# W506X.net
KiCad netlist of a schematic drawn in EAGLE
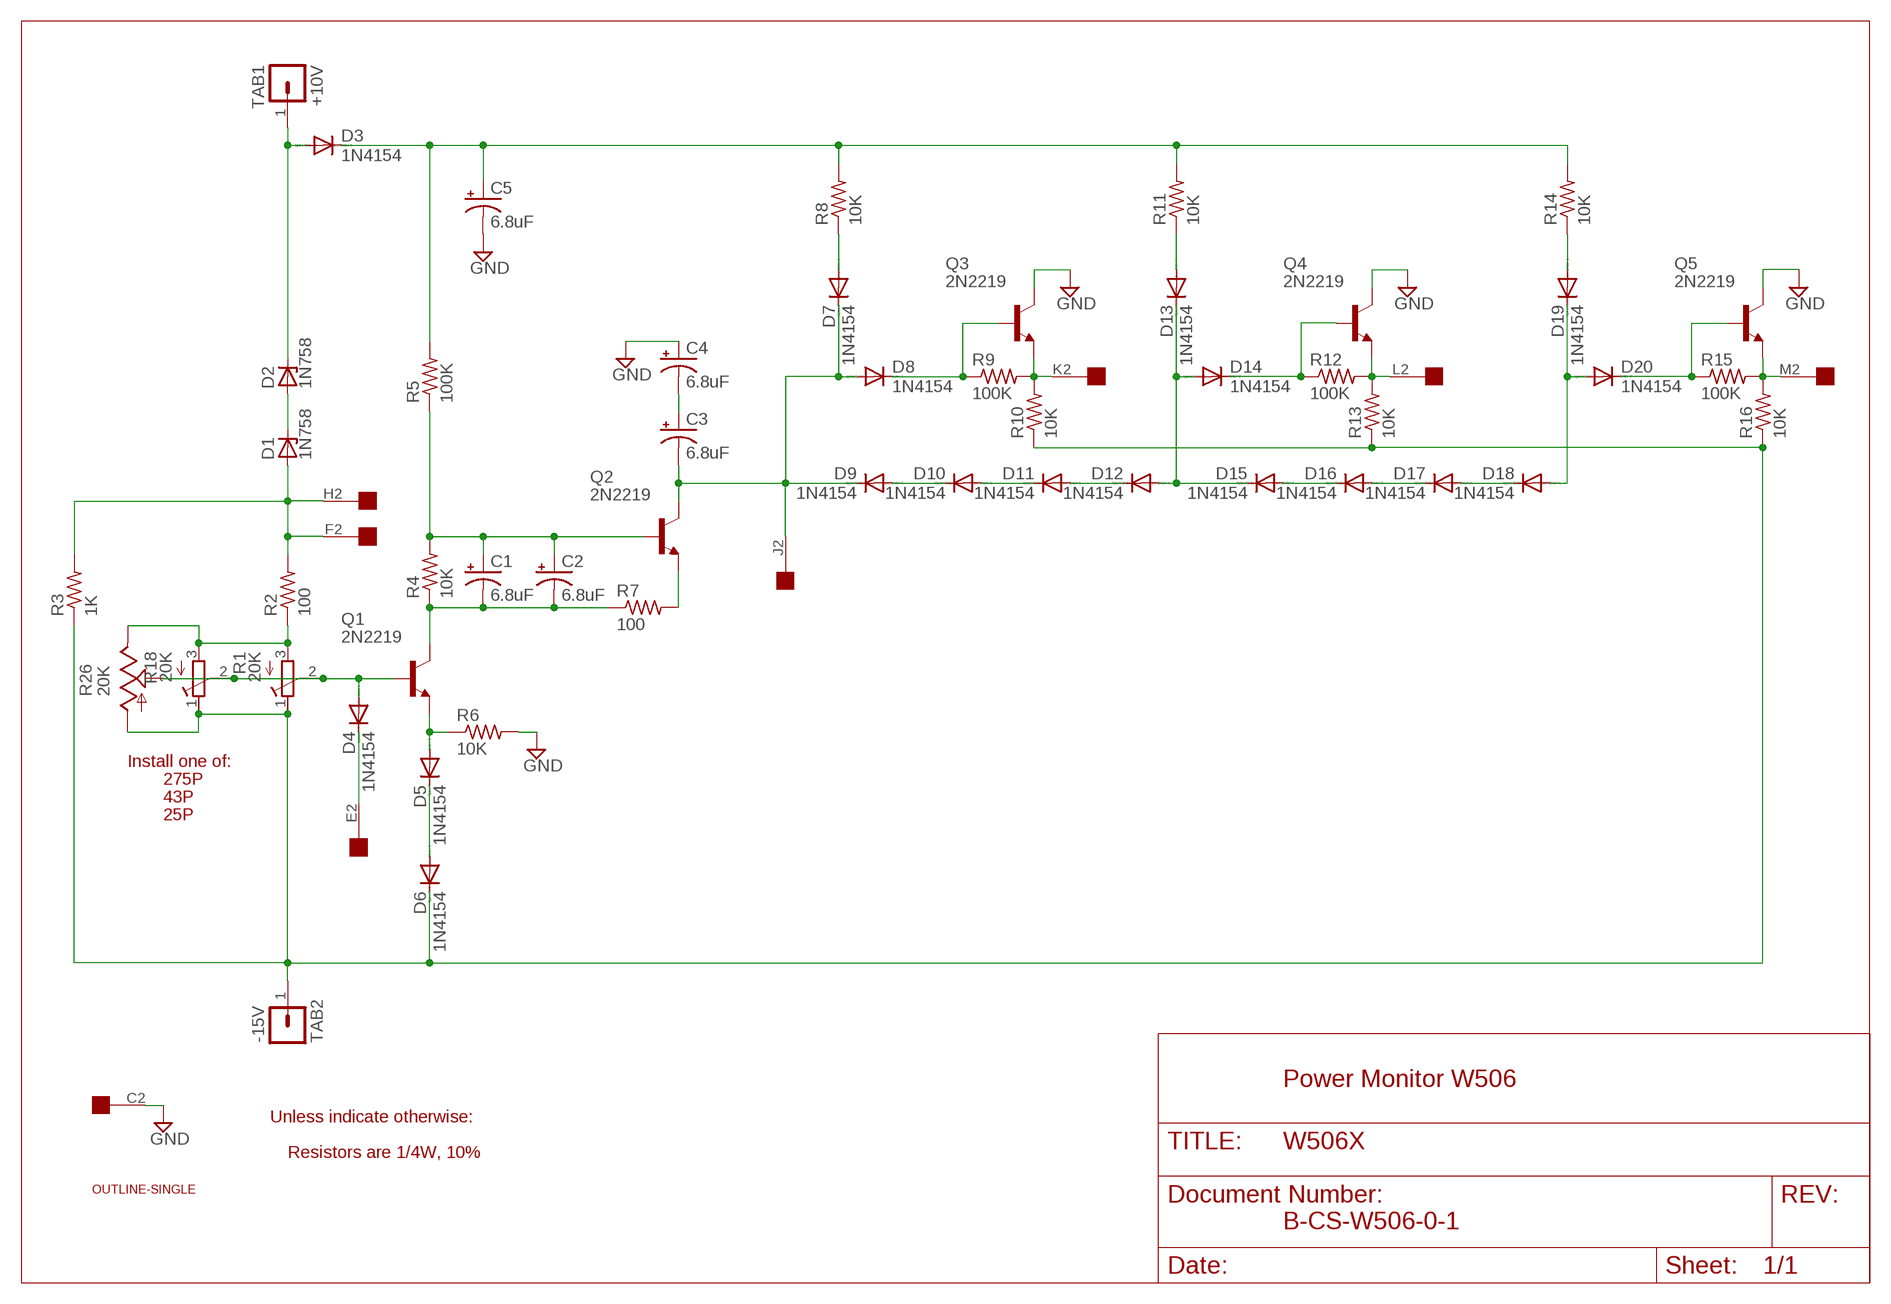
[diagram p0: schematic, sheet 1]

(export (version "E")
  (design (tool "Eeschema 10.0.6"))
  (components
    (comp (ref "C1")
      (value "6.8uF")
      (footprint "eagle-import:E15-5")
      (libsource (lib "eagle-import") (part "CPOL-USE15-5AXIAL"))
    )
    (comp (ref "C2")
      (value "6.8uF")
      (footprint "eagle-import:E15-5")
      (libsource (lib "eagle-import") (part "CPOL-USE15-5AXIAL"))
    )
    (comp (ref "C3")
      (value "6.8uF")
      (footprint "eagle-import:E15-5")
      (libsource (lib "eagle-import") (part "CPOL-USE15-5AXIAL"))
    )
    (comp (ref "C4")
      (value "6.8uF")
      (footprint "eagle-import:E15-5")
      (libsource (lib "eagle-import") (part "CPOL-USE15-5AXIAL"))
    )
    (comp (ref "C5")
      (value "6.8uF")
      (footprint "eagle-import:E15-5")
      (libsource (lib "eagle-import") (part "CPOL-USE15-5AXIAL"))
    )
    (comp (ref "D1")
      (value "1N758")
      (footprint "eagle-import:DO35Z10")
      (libsource (lib "eagle-import") (part "ZENER-DIODEDO35Z10"))
    )
    (comp (ref "D2")
      (value "1N758")
      (footprint "eagle-import:DO35Z10")
      (libsource (lib "eagle-import") (part "ZENER-DIODEDO35Z10"))
    )
    (comp (ref "D3")
      (value "1N4154")
      (footprint "eagle-import:DO35-10")
      (libsource (lib "eagle-import") (part "1N4148DO35-10"))
    )
    (comp (ref "D4")
      (value "1N4154")
      (footprint "eagle-import:DO35-10")
      (libsource (lib "eagle-import") (part "1N4148DO35-10"))
    )
    (comp (ref "D5")
      (value "1N4154")
      (footprint "eagle-import:DO35-10")
      (libsource (lib "eagle-import") (part "1N4148DO35-10"))
    )
    (comp (ref "D6")
      (value "1N4154")
      (footprint "eagle-import:DO35-10")
      (libsource (lib "eagle-import") (part "1N4148DO35-10"))
    )
    (comp (ref "D7")
      (value "1N4154")
      (footprint "eagle-import:DO35-10")
      (libsource (lib "eagle-import") (part "1N4148DO35-10"))
    )
    (comp (ref "D8")
      (value "1N4154")
      (footprint "eagle-import:DO35-10")
      (libsource (lib "eagle-import") (part "1N4148DO35-10"))
    )
    (comp (ref "D9")
      (value "1N4154")
      (footprint "eagle-import:DO35-10")
      (libsource (lib "eagle-import") (part "1N4148DO35-10"))
    )
    (comp (ref "D10")
      (value "1N4154")
      (footprint "eagle-import:DO35-10")
      (libsource (lib "eagle-import") (part "1N4148DO35-10"))
    )
    (comp (ref "D11")
      (value "1N4154")
      (footprint "eagle-import:DO35-10")
      (libsource (lib "eagle-import") (part "1N4148DO35-10"))
    )
    (comp (ref "D12")
      (value "1N4154")
      (footprint "eagle-import:DO35-10")
      (libsource (lib "eagle-import") (part "1N4148DO35-10"))
    )
    (comp (ref "D13")
      (value "1N4154")
      (footprint "eagle-import:DO35-10")
      (libsource (lib "eagle-import") (part "1N4148DO35-10"))
    )
    (comp (ref "D14")
      (value "1N4154")
      (footprint "eagle-import:DO35-10")
      (libsource (lib "eagle-import") (part "1N4148DO35-10"))
    )
    (comp (ref "D15")
      (value "1N4154")
      (footprint "eagle-import:DO35-10")
      (libsource (lib "eagle-import") (part "1N4148DO35-10"))
    )
    (comp (ref "D16")
      (value "1N4154")
      (footprint "eagle-import:DO35-10")
      (libsource (lib "eagle-import") (part "1N4148DO35-10"))
    )
    (comp (ref "D17")
      (value "1N4154")
      (footprint "eagle-import:DO35-10")
      (libsource (lib "eagle-import") (part "1N4148DO35-10"))
    )
    (comp (ref "D18")
      (value "1N4154")
      (footprint "eagle-import:DO35-10")
      (libsource (lib "eagle-import") (part "1N4148DO35-10"))
    )
    (comp (ref "D19")
      (value "1N4154")
      (footprint "eagle-import:DO35-10")
      (libsource (lib "eagle-import") (part "1N4148DO35-10"))
    )
    (comp (ref "D20")
      (value "1N4154")
      (footprint "eagle-import:DO35-10")
      (libsource (lib "eagle-import") (part "1N4148DO35-10"))
    )
    (comp (ref "EDGE")
      (value "EDGE-1")
      (footprint "eagle-import:EDGE-CON1")
      (libsource (lib "eagle-import") (part "EDGE-1"))
    )
    (comp (ref "Q1")
      (value "2N2219")
      (footprint "eagle-import:TO5")
      (libsource (lib "eagle-import") (part "2N2102"))
    )
    (comp (ref "Q2")
      (value "2N2219")
      (footprint "eagle-import:TO5")
      (libsource (lib "eagle-import") (part "2N2102"))
    )
    (comp (ref "Q3")
      (value "2N2219")
      (footprint "eagle-import:TO5")
      (libsource (lib "eagle-import") (part "2N2102"))
    )
    (comp (ref "Q4")
      (value "2N2219")
      (footprint "eagle-import:TO5")
      (libsource (lib "eagle-import") (part "2N2102"))
    )
    (comp (ref "Q5")
      (value "2N2219")
      (footprint "eagle-import:TO5")
      (libsource (lib "eagle-import") (part "2N2102"))
    )
    (comp (ref "R1")
      (value "20K")
      (footprint "eagle-import:3006Y")
      (libsource (lib "eagle-import") (part "275P"))
    )
    (comp (ref "R2")
      (value "100")
      (footprint "eagle-import:0207_10")
      (libsource (lib "eagle-import") (part "R-US_0207/10"))
    )
    (comp (ref "R3")
      (value "1K")
      (footprint "eagle-import:0207_10")
      (libsource (lib "eagle-import") (part "R-US_0207/10"))
    )
    (comp (ref "R4")
      (value "10K")
      (footprint "eagle-import:0207_10")
      (libsource (lib "eagle-import") (part "R-US_0207/10"))
    )
    (comp (ref "R5")
      (value "100K")
      (footprint "eagle-import:0207_10")
      (libsource (lib "eagle-import") (part "R-US_0207/10"))
    )
    (comp (ref "R6")
      (value "10K")
      (footprint "eagle-import:0207_10")
      (libsource (lib "eagle-import") (part "R-US_0207/10"))
    )
    (comp (ref "R7")
      (value "100")
      (footprint "eagle-import:0207_10")
      (libsource (lib "eagle-import") (part "R-US_0207/10"))
    )
    (comp (ref "R8")
      (value "10K")
      (footprint "eagle-import:0207_10")
      (libsource (lib "eagle-import") (part "R-US_0207/10"))
    )
    (comp (ref "R9")
      (value "100K")
      (footprint "eagle-import:0207_10")
      (libsource (lib "eagle-import") (part "R-US_0207/10"))
    )
    (comp (ref "R10")
      (value "10K")
      (footprint "eagle-import:0207_10")
      (libsource (lib "eagle-import") (part "R-US_0207/10"))
    )
    (comp (ref "R11")
      (value "10K")
      (footprint "eagle-import:0207_10")
      (libsource (lib "eagle-import") (part "R-US_0207/10"))
    )
    (comp (ref "R12")
      (value "100K")
      (footprint "eagle-import:0207_10")
      (libsource (lib "eagle-import") (part "R-US_0207/10"))
    )
    (comp (ref "R13")
      (value "10K")
      (footprint "eagle-import:0207_10")
      (libsource (lib "eagle-import") (part "R-US_0207/10"))
    )
    (comp (ref "R14")
      (value "10K")
      (footprint "eagle-import:0207_10")
      (libsource (lib "eagle-import") (part "R-US_0207/10"))
    )
    (comp (ref "R15")
      (value "100K")
      (footprint "eagle-import:0207_10")
      (libsource (lib "eagle-import") (part "R-US_0207/10"))
    )
    (comp (ref "R16")
      (value "10K")
      (footprint "eagle-import:0207_10")
      (libsource (lib "eagle-import") (part "R-US_0207/10"))
    )
    (comp (ref "R18")
      (value "20K")
      (footprint "eagle-import:RTRIM43P")
      (libsource (lib "eagle-import") (part "R-TRIMM43P"))
    )
    (comp (ref "R26")
      (value "20K")
      (footprint "eagle-import:B25P")
      (libsource (lib "eagle-import") (part "TRIM_US-B25P"))
    )
    (comp (ref "TAB1")
      (value "+10V")
      (footprint "eagle-import:SPADELUG")
      (libsource (lib "eagle-import") (part "LUG"))
    )
    (comp (ref "TAB2")
      (value "-15V")
      (footprint "eagle-import:SPADELUG")
      (libsource (lib "eagle-import") (part "LUG"))
    )
    (comp (ref "U$1")
      (value "OUTLINE-SINGLE")
      (footprint "eagle-import:SINGLE")
      (libsource (lib "eagle-import") (part "OUTLINE-SINGLE"))
    )
  )
  (nets
    (net (code "1") (name "GND") (class "Default")
      (node (ref "C4") (pin "+") (pinfunction "+_+") (pintype "passive"))
      (node (ref "C5") (pin "-") (pinfunction "-_-") (pintype "passive"))
      (node (ref "EDGE") (pin "C2") (pinfunction "1_C2") (pintype "bidirectional"))
      (node (ref "Q3") (pin "3") (pinfunction "C_3") (pintype "passive"))
      (node (ref "Q4") (pin "3") (pinfunction "C_3") (pintype "passive"))
      (node (ref "Q5") (pin "3") (pinfunction "C_3") (pintype "passive"))
      (node (ref "R6") (pin "2") (pinfunction "2_2") (pintype "passive"))
    )
    (net (code "2") (name "Net-(C3-Pad+)") (class "Default")
      (node (ref "C3") (pin "+") (pinfunction "+_+") (pintype "passive"))
      (node (ref "C4") (pin "-") (pinfunction "-_-") (pintype "passive"))
    )
    (net (code "3") (name "Net-(C5-Pad+)") (class "Default")
      (node (ref "C5") (pin "+") (pinfunction "+_+") (pintype "passive"))
      (node (ref "D3") (pin "C") (pinfunction "C_C") (pintype "passive"))
      (node (ref "R11") (pin "2") (pinfunction "2_2") (pintype "passive"))
      (node (ref "R14") (pin "2") (pinfunction "2_2") (pintype "passive"))
      (node (ref "R5") (pin "2") (pinfunction "2_2") (pintype "passive"))
      (node (ref "R8") (pin "2") (pinfunction "2_2") (pintype "passive"))
    )
    (net (code "4") (name "Net-(D1-PadC)") (class "Default")
      (node (ref "D1") (pin "C") (pinfunction "C_C") (pintype "passive"))
      (node (ref "D2") (pin "A") (pinfunction "A_A") (pintype "passive"))
    )
    (net (code "5") (name "Net-(D2-PadC)") (class "Default")
      (node (ref "D2") (pin "C") (pinfunction "C_C") (pintype "passive"))
      (node (ref "D3") (pin "A") (pinfunction "A_A") (pintype "passive"))
      (node (ref "TAB1") (pin "1") (pinfunction "1_1") (pintype "passive"))
    )
    (net (code "6") (name "Net-(D5-PadC)") (class "Default")
      (node (ref "D5") (pin "C") (pinfunction "C_C") (pintype "passive"))
      (node (ref "D6") (pin "A") (pinfunction "A_A") (pintype "passive"))
    )
    (net (code "7") (name "Net-(D7-PadA)") (class "Default")
      (node (ref "D7") (pin "A") (pinfunction "A_A") (pintype "passive"))
      (node (ref "R8") (pin "1") (pinfunction "1_1") (pintype "passive"))
    )
    (net (code "8") (name "Net-(D10-PadA)") (class "Default")
      (node (ref "D10") (pin "A") (pinfunction "A_A") (pintype "passive"))
      (node (ref "D11") (pin "C") (pinfunction "C_C") (pintype "passive"))
    )
    (net (code "9") (name "Net-(D10-PadC)") (class "Default")
      (node (ref "D10") (pin "C") (pinfunction "C_C") (pintype "passive"))
      (node (ref "D9") (pin "A") (pinfunction "A_A") (pintype "passive"))
    )
    (net (code "10") (name "Net-(D11-PadA)") (class "Default")
      (node (ref "D11") (pin "A") (pinfunction "A_A") (pintype "passive"))
      (node (ref "D12") (pin "C") (pinfunction "C_C") (pintype "passive"))
    )
    (net (code "11") (name "Net-(D12-PadA)") (class "Default")
      (node (ref "D12") (pin "A") (pinfunction "A_A") (pintype "passive"))
      (node (ref "D13") (pin "C") (pinfunction "C_C") (pintype "passive"))
      (node (ref "D14") (pin "A") (pinfunction "A_A") (pintype "passive"))
      (node (ref "D15") (pin "C") (pinfunction "C_C") (pintype "passive"))
    )
    (net (code "12") (name "Net-(D13-PadA)") (class "Default")
      (node (ref "D13") (pin "A") (pinfunction "A_A") (pintype "passive"))
      (node (ref "R11") (pin "1") (pinfunction "1_1") (pintype "passive"))
    )
    (net (code "13") (name "Net-(D15-PadA)") (class "Default")
      (node (ref "D15") (pin "A") (pinfunction "A_A") (pintype "passive"))
      (node (ref "D16") (pin "C") (pinfunction "C_C") (pintype "passive"))
    )
    (net (code "14") (name "Net-(D16-PadA)") (class "Default")
      (node (ref "D16") (pin "A") (pinfunction "A_A") (pintype "passive"))
      (node (ref "D17") (pin "C") (pinfunction "C_C") (pintype "passive"))
    )
    (net (code "15") (name "Net-(D17-PadA)") (class "Default")
      (node (ref "D17") (pin "A") (pinfunction "A_A") (pintype "passive"))
      (node (ref "D18") (pin "C") (pinfunction "C_C") (pintype "passive"))
    )
    (net (code "16") (name "Net-(D18-PadA)") (class "Default")
      (node (ref "D18") (pin "A") (pinfunction "A_A") (pintype "passive"))
      (node (ref "D19") (pin "C") (pinfunction "C_C") (pintype "passive"))
      (node (ref "D20") (pin "A") (pinfunction "A_A") (pintype "passive"))
    )
    (net (code "17") (name "Net-(D19-PadA)") (class "Default")
      (node (ref "D19") (pin "A") (pinfunction "A_A") (pintype "passive"))
      (node (ref "R14") (pin "1") (pinfunction "1_1") (pintype "passive"))
    )
    (net (code "18") (name "Net-(EDGEE-1)") (class "Default")
      (node (ref "D4") (pin "C") (pinfunction "C_C") (pintype "passive"))
      (node (ref "EDGE") (pin "E2") (pinfunction "1_E2") (pintype "bidirectional"))
    )
    (net (code "19") (name "Net-(EDGEF-1)") (class "Default")
      (node (ref "D1") (pin "A") (pinfunction "A_A") (pintype "passive"))
      (node (ref "EDGE") (pin "F2") (pinfunction "1_F2") (pintype "bidirectional"))
      (node (ref "EDGE") (pin "H2") (pinfunction "1_H2") (pintype "bidirectional"))
      (node (ref "R2") (pin "2") (pinfunction "2_2") (pintype "passive"))
      (node (ref "R3") (pin "2") (pinfunction "2_2") (pintype "passive"))
    )
    (net (code "20") (name "Net-(EDGEH-1)") (class "Default")
      (node (ref "C3") (pin "-") (pinfunction "-_-") (pintype "passive"))
      (node (ref "D7") (pin "C") (pinfunction "C_C") (pintype "passive"))
      (node (ref "D8") (pin "A") (pinfunction "A_A") (pintype "passive"))
      (node (ref "D9") (pin "C") (pinfunction "C_C") (pintype "passive"))
      (node (ref "EDGE") (pin "J2") (pinfunction "1_J2") (pintype "bidirectional"))
      (node (ref "Q2") (pin "3") (pinfunction "C_3") (pintype "passive"))
    )
    (net (code "21") (name "Net-(EDGEI-1)") (class "Default")
      (node (ref "EDGE") (pin "K2") (pinfunction "1_K2") (pintype "bidirectional"))
      (node (ref "Q3") (pin "1") (pinfunction "E_1") (pintype "passive"))
      (node (ref "R10") (pin "2") (pinfunction "2_2") (pintype "passive"))
      (node (ref "R9") (pin "2") (pinfunction "2_2") (pintype "passive"))
    )
    (net (code "22") (name "Net-(EDGEJ-1)") (class "Default")
      (node (ref "EDGE") (pin "L2") (pinfunction "1_L2") (pintype "bidirectional"))
      (node (ref "Q4") (pin "1") (pinfunction "E_1") (pintype "passive"))
      (node (ref "R12") (pin "2") (pinfunction "2_2") (pintype "passive"))
      (node (ref "R13") (pin "2") (pinfunction "2_2") (pintype "passive"))
    )
    (net (code "23") (name "Net-(EDGEK-1)") (class "Default")
      (node (ref "EDGE") (pin "M2") (pinfunction "1_M2") (pintype "bidirectional"))
      (node (ref "Q5") (pin "1") (pinfunction "E_1") (pintype "passive"))
      (node (ref "R15") (pin "2") (pinfunction "2_2") (pintype "passive"))
      (node (ref "R16") (pin "2") (pinfunction "2_2") (pintype "passive"))
    )
    (net (code "24") (name "Net-(Q1-B)") (class "Default")
      (node (ref "D4") (pin "A") (pinfunction "A_A") (pintype "passive"))
      (node (ref "Q1") (pin "2") (pinfunction "B_2") (pintype "passive"))
      (node (ref "R1") (pin "2") (pinfunction "S_2") (pintype "passive"))
      (node (ref "R18") (pin "2") (pinfunction "S_2") (pintype "passive"))
      (node (ref "R26") (pin "S") (pinfunction "S_S") (pintype "passive"))
    )
    (net (code "25") (name "Net-(Q1-C)") (class "Default")
      (node (ref "C1") (pin "-") (pinfunction "-_-") (pintype "passive"))
      (node (ref "C2") (pin "-") (pinfunction "-_-") (pintype "passive"))
      (node (ref "Q1") (pin "3") (pinfunction "C_3") (pintype "passive"))
      (node (ref "R4") (pin "1") (pinfunction "1_1") (pintype "passive"))
      (node (ref "R7") (pin "1") (pinfunction "1_1") (pintype "passive"))
    )
    (net (code "26") (name "Net-(Q1-E)") (class "Default")
      (node (ref "D5") (pin "A") (pinfunction "A_A") (pintype "passive"))
      (node (ref "Q1") (pin "1") (pinfunction "E_1") (pintype "passive"))
      (node (ref "R6") (pin "1") (pinfunction "1_1") (pintype "passive"))
    )
    (net (code "27") (name "Net-(Q2-B)") (class "Default")
      (node (ref "C1") (pin "+") (pinfunction "+_+") (pintype "passive"))
      (node (ref "C2") (pin "+") (pinfunction "+_+") (pintype "passive"))
      (node (ref "Q2") (pin "2") (pinfunction "B_2") (pintype "passive"))
      (node (ref "R4") (pin "2") (pinfunction "2_2") (pintype "passive"))
      (node (ref "R5") (pin "1") (pinfunction "1_1") (pintype "passive"))
    )
    (net (code "28") (name "Net-(Q2-E)") (class "Default")
      (node (ref "Q2") (pin "1") (pinfunction "E_1") (pintype "passive"))
      (node (ref "R7") (pin "2") (pinfunction "2_2") (pintype "passive"))
    )
    (net (code "29") (name "Net-(Q3-B)") (class "Default")
      (node (ref "D8") (pin "C") (pinfunction "C_C") (pintype "passive"))
      (node (ref "Q3") (pin "2") (pinfunction "B_2") (pintype "passive"))
      (node (ref "R9") (pin "1") (pinfunction "1_1") (pintype "passive"))
    )
    (net (code "30") (name "Net-(Q4-B)") (class "Default")
      (node (ref "D14") (pin "C") (pinfunction "C_C") (pintype "passive"))
      (node (ref "Q4") (pin "2") (pinfunction "B_2") (pintype "passive"))
      (node (ref "R12") (pin "1") (pinfunction "1_1") (pintype "passive"))
    )
    (net (code "31") (name "Net-(Q5-B)") (class "Default")
      (node (ref "D20") (pin "C") (pinfunction "C_C") (pintype "passive"))
      (node (ref "Q5") (pin "2") (pinfunction "B_2") (pintype "passive"))
      (node (ref "R15") (pin "1") (pinfunction "1_1") (pintype "passive"))
    )
    (net (code "32") (name "Net-(R1-A)") (class "Default")
      (node (ref "D6") (pin "C") (pinfunction "C_C") (pintype "passive"))
      (node (ref "R1") (pin "1") (pinfunction "A_1") (pintype "passive"))
      (node (ref "R10") (pin "1") (pinfunction "1_1") (pintype "passive"))
      (node (ref "R13") (pin "1") (pinfunction "1_1") (pintype "passive"))
      (node (ref "R16") (pin "1") (pinfunction "1_1") (pintype "passive"))
      (node (ref "R18") (pin "1") (pinfunction "E_1") (pintype "passive"))
      (node (ref "R26") (pin "A") (pinfunction "A_A") (pintype "passive"))
      (node (ref "R3") (pin "1") (pinfunction "1_1") (pintype "passive"))
      (node (ref "TAB2") (pin "1") (pinfunction "1_1") (pintype "passive"))
    )
    (net (code "33") (name "Net-(R1-E)") (class "Default")
      (node (ref "R1") (pin "3") (pinfunction "E_3") (pintype "passive"))
      (node (ref "R18") (pin "3") (pinfunction "A_3") (pintype "passive"))
      (node (ref "R2") (pin "1") (pinfunction "1_1") (pintype "passive"))
      (node (ref "R26") (pin "E") (pinfunction "E_E") (pintype "passive"))
    )
  )
)
